# jack_driver_1.net
KiCad netlist of a schematic drawn in Altium Designer
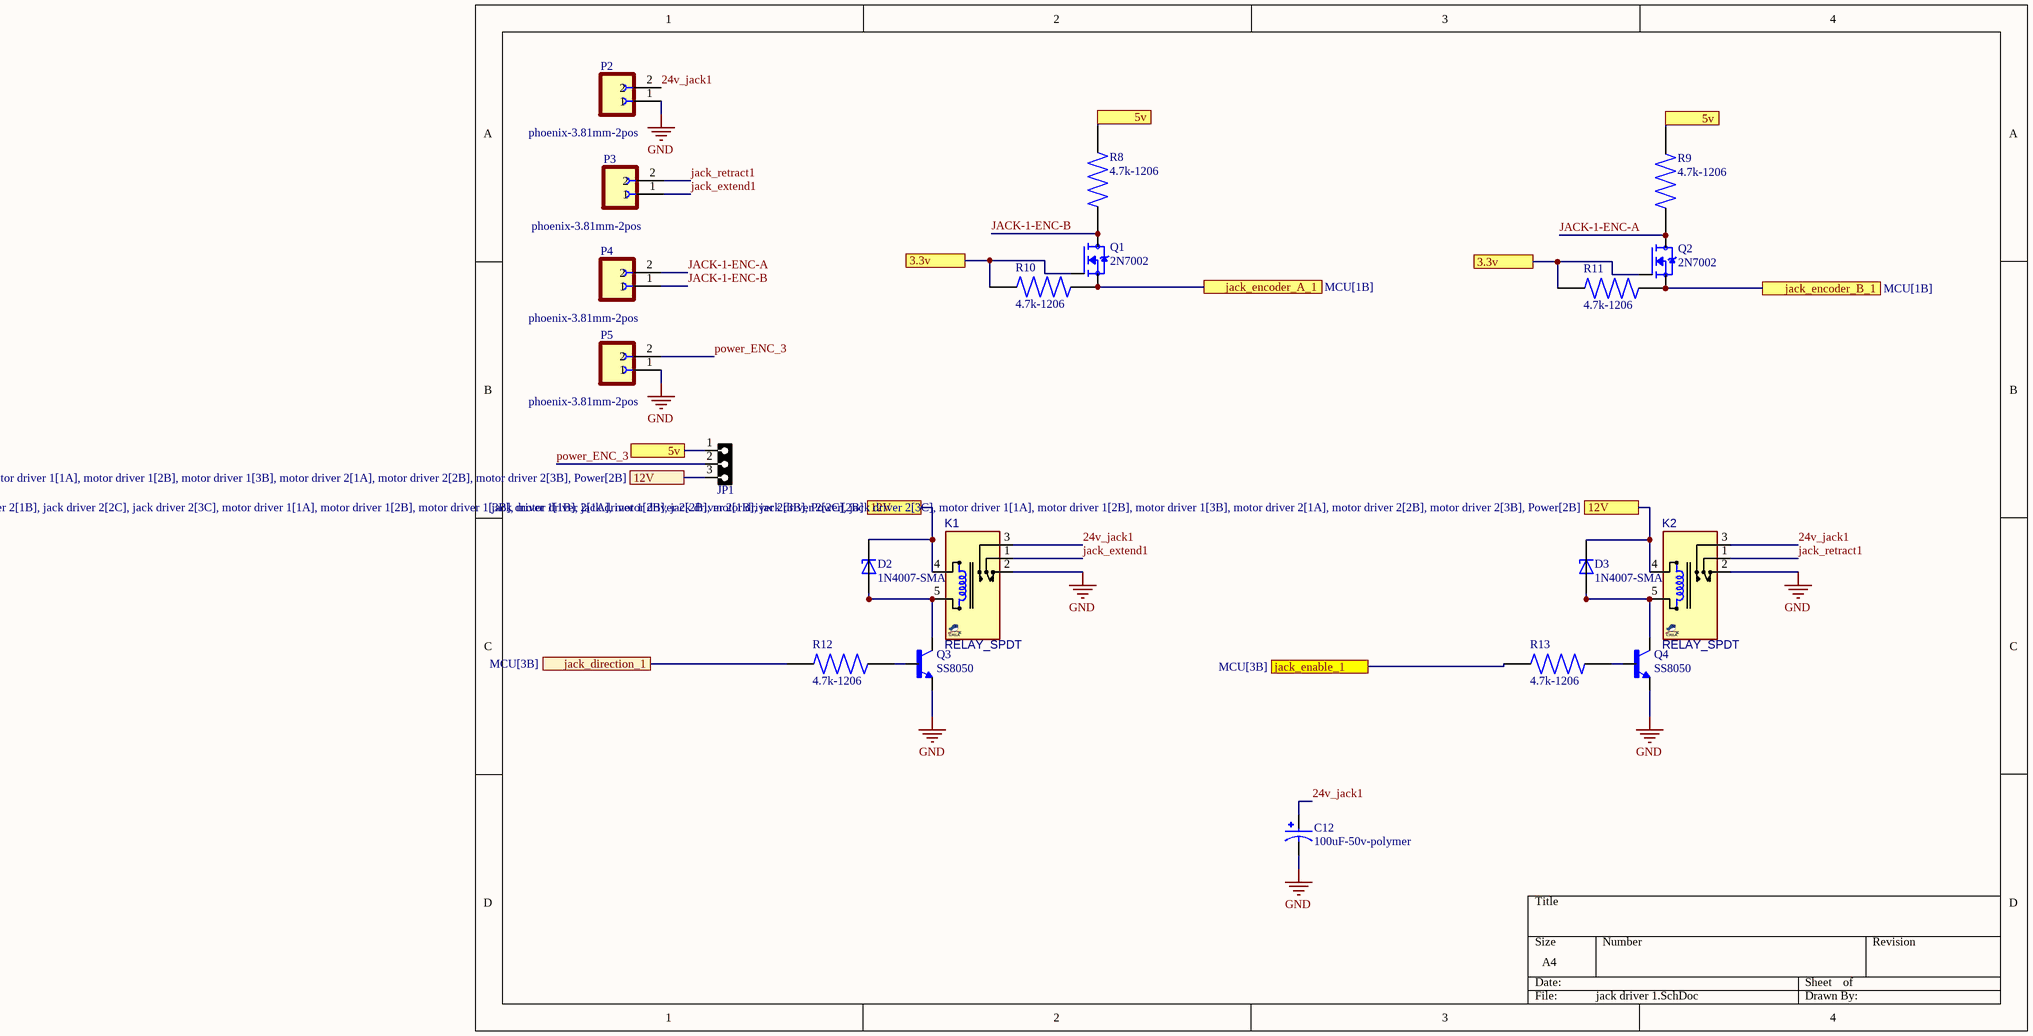
[diagram p0: jack driver 1.SchDoc]

(export (version "E")
  (design (tool "Eeschema 10.0.6"))
  (components
    (comp (ref "C12")
      (value "100uF-50v-polymer")
      (footprint "CAP_EEEFN1H101L")
      (description "CAP ALUM 100UF 20% 50V SMD")
      (fields (field (name "MF") "Panasonic") (field (name "MP") "EEEFN1H101L"))
      (libsource (lib "100uF_50v") (part "EEEFN1H101L"))
    )
    (comp (ref "D2")
      (value "1N4007-SMA")
      (footprint "DIOM4325X250N")
      (description "400W, 30.4V, 5%, Unidirectional, TVS")
      (fields (field (name "MF") "Taiwan Semiconductor") (field (name "MP") "SMAJ26A"))
      (libsource (lib "diode-sma") (part "SMAJ26A"))
    )
    (comp (ref "D3")
      (value "1N4007-SMA")
      (footprint "DIOM4325X250N")
      (description "400W, 30.4V, 5%, Unidirectional, TVS")
      (fields (field (name "MF") "Taiwan Semiconductor") (field (name "MP") "SMAJ26A"))
      (libsource (lib "diode-sma") (part "SMAJ26A"))
    )
    (comp (ref "JP1")
      (value "HDRF3")
      (footprint "HDRLP_F_1X3")
      (description "CONN, HEADER, Male, pitch: 2.54mm, 3POS")
      (libsource (lib "conn_2.54mm_lp") (part "HDRLP_F_1X3"))
    )
    (comp (ref "K1")
      (value "RELAY_SPDT")
      (footprint "REL_SPDT_5_1512")
      (description "Relay, SPDT, 5P, 15.4X12.1mm, 16V/30A")
      (fields (field (name "MANF") "OMRON") (field (name "MANF_P#") "G8QN-1C4 DC12"))
      (libsource (lib "relay") (part "RELAY_SPDT_5_1512_G8QN"))
    )
    (comp (ref "K2")
      (value "RELAY_SPDT")
      (footprint "REL_SPDT_5_1512")
      (description "Relay, SPDT, 5P, 15.4X12.1mm, 16V/30A")
      (fields (field (name "MANF") "OMRON") (field (name "MANF_P#") "G8QN-1C4 DC12"))
      (libsource (lib "relay") (part "RELAY_SPDT_5_1512_G8QN"))
    )
    (comp (ref "P2")
      (value "phoenix-3.81mm-2pos")
      (footprint "PHOENIX_1803578")
      (description "2 Position Terminal Block Plug, Female Sockets 0.150 (3.81mm) 180Â° Free Hanging (In-Line)")
      (fields (field (name "MF") "Phoenix Contact") (field (name "MP") "1803578"))
      (libsource (lib "terminal-phoenix-3.81mm-2pos") (part "1803578"))
    )
    (comp (ref "P3")
      (value "phoenix-3.81mm-2pos")
      (footprint "PHOENIX_1803578")
      (description "2 Position Terminal Block Plug, Female Sockets 0.150 (3.81mm) 180Â° Free Hanging (In-Line)")
      (fields (field (name "MF") "Phoenix Contact") (field (name "MP") "1803578"))
      (libsource (lib "terminal-phoenix-3.81mm-2pos") (part "1803578"))
    )
    (comp (ref "P4")
      (value "phoenix-3.81mm-2pos")
      (footprint "PHOENIX_1803578")
      (description "2 Position Terminal Block Plug, Female Sockets 0.150 (3.81mm) 180Â° Free Hanging (In-Line)")
      (fields (field (name "MF") "Phoenix Contact") (field (name "MP") "1803578"))
      (libsource (lib "terminal-phoenix-3.81mm-2pos") (part "1803578"))
    )
    (comp (ref "P5")
      (value "phoenix-3.81mm-2pos")
      (footprint "PHOENIX_1803578")
      (description "2 Position Terminal Block Plug, Female Sockets 0.150 (3.81mm) 180Â° Free Hanging (In-Line)")
      (fields (field (name "MF") "Phoenix Contact") (field (name "MP") "1803578"))
      (libsource (lib "terminal-phoenix-3.81mm-2pos") (part "1803578"))
    )
    (comp (ref "Q1")
      (value "2N7002")
      (footprint "SOT95P240X111-3N")
      (description "N-Channel 60V 280mA (Ta) 350mW (Ta) Surface Mount SOT-23-3 (TO-236)")
      (fields (field (name "MF") "{'manufacturer': u'onsemi'}"))
      (libsource (lib "2N7002-SOT23") (part "2N7002"))
    )
    (comp (ref "Q2")
      (value "2N7002")
      (footprint "SOT95P240X111-3N")
      (description "N-Channel 60V 280mA (Ta) 350mW (Ta) Surface Mount SOT-23-3 (TO-236)")
      (fields (field (name "MF") "{'manufacturer': u'onsemi'}"))
      (libsource (lib "2N7002-SOT23") (part "2N7002"))
    )
    (comp (ref "Q3")
      (value "SS8050")
      (footprint "TRANS_SS8050-G")
      (description "Bipolar (BJT) Transistor NPN 25 V 1.5 A 100MHz 300 mW Surface Mount SOT-23-3")
      (fields (field (name "DIGI-KEY_PART_NUMBER") "641-1790-2-ND") (field (name "MP") "SS8050G"))
      (libsource (lib "SS8050-G") (part "SS8050-G"))
    )
    (comp (ref "Q4")
      (value "SS8050")
      (footprint "TRANS_SS8050-G")
      (description "Bipolar (BJT) Transistor NPN 25 V 1.5 A 100MHz 300 mW Surface Mount SOT-23-3")
      (fields (field (name "DIGI-KEY_PART_NUMBER") "641-1790-2-ND") (field (name "MP") "SS8050G"))
      (libsource (lib "SS8050-G") (part "SS8050-G"))
    )
    (comp (ref "R8")
      (value "4.7k-1206")
      (footprint "RESC3015X65N")
      (description "Res Thin Film 1206 10K Ohm 0.1% 1/8W Â±25ppm/Â°C Molded SMD SMD Paper T/R")
      (fields (field (name "MF") "TE Connectivity") (field (name "MP") "CPF1206B10KE1"))
      (libsource (lib "resistor-1206") (part "CPF1206B10KE1"))
    )
    (comp (ref "R9")
      (value "4.7k-1206")
      (footprint "RESC3015X65N")
      (description "Res Thin Film 1206 10K Ohm 0.1% 1/8W Â±25ppm/Â°C Molded SMD SMD Paper T/R")
      (fields (field (name "MF") "TE Connectivity") (field (name "MP") "CPF1206B10KE1"))
      (libsource (lib "resistor-1206") (part "CPF1206B10KE1"))
    )
    (comp (ref "R10")
      (value "4.7k-1206")
      (footprint "RESC3015X65N")
      (description "Res Thin Film 1206 10K Ohm 0.1% 1/8W Â±25ppm/Â°C Molded SMD SMD Paper T/R")
      (fields (field (name "MF") "TE Connectivity") (field (name "MP") "CPF1206B10KE1"))
      (libsource (lib "resistor-1206") (part "CPF1206B10KE1"))
    )
    (comp (ref "R11")
      (value "4.7k-1206")
      (footprint "RESC3015X65N")
      (description "Res Thin Film 1206 10K Ohm 0.1% 1/8W Â±25ppm/Â°C Molded SMD SMD Paper T/R")
      (fields (field (name "MF") "TE Connectivity") (field (name "MP") "CPF1206B10KE1"))
      (libsource (lib "resistor-1206") (part "CPF1206B10KE1"))
    )
    (comp (ref "R12")
      (value "4.7k-1206")
      (footprint "RESC3015X65N")
      (description "Res Thin Film 1206 10K Ohm 0.1% 1/8W Â±25ppm/Â°C Molded SMD SMD Paper T/R")
      (fields (field (name "MF") "TE Connectivity") (field (name "MP") "CPF1206B10KE1"))
      (libsource (lib "resistor-1206") (part "CPF1206B10KE1"))
    )
    (comp (ref "R13")
      (value "4.7k-1206")
      (footprint "RESC3015X65N")
      (description "Res Thin Film 1206 10K Ohm 0.1% 1/8W Â±25ppm/Â°C Molded SMD SMD Paper T/R")
      (fields (field (name "MF") "TE Connectivity") (field (name "MP") "CPF1206B10KE1"))
      (libsource (lib "resistor-1206") (part "CPF1206B10KE1"))
    )
  )
  (nets
    (net (code "1") (name "/3.3v") (class "Default")
      (node (ref "Q1") (pin "1") (pinfunction "G_1") (pintype "passive"))
      (node (ref "Q2") (pin "1") (pinfunction "G_1") (pintype "passive"))
      (node (ref "R10") (pin "2") (pinfunction "2_2") (pintype "passive"))
      (node (ref "R11") (pin "2") (pinfunction "2_2") (pintype "passive"))
    )
    (net (code "2") (name "/5v") (class "Default")
      (node (ref "JP1") (pin "1") (pinfunction "1_1") (pintype "passive"))
      (node (ref "R8") (pin "2") (pinfunction "2_2") (pintype "passive"))
      (node (ref "R9") (pin "2") (pinfunction "2_2") (pintype "passive"))
    )
    (net (code "3") (name "/12V") (class "Default")
      (node (ref "D2") (pin "C") (pinfunction "C_C") (pintype "passive"))
      (node (ref "D3") (pin "C") (pinfunction "C_C") (pintype "passive"))
      (node (ref "JP1") (pin "3") (pinfunction "3_3") (pintype "passive"))
      (node (ref "K1") (pin "4") (pinfunction "T1_4") (pintype "passive"))
      (node (ref "K2") (pin "4") (pinfunction "T1_4") (pintype "passive"))
    )
    (net (code "4") (name "/24v_jack1") (class "Default")
      (node (ref "C12") (pin "1") (pinfunction "1_1") (pintype "passive"))
      (node (ref "K1") (pin "3") (pinfunction "NO_3") (pintype "passive"))
      (node (ref "K2") (pin "3") (pinfunction "NO_3") (pintype "passive"))
      (node (ref "P2") (pin "2") (pinfunction "2_2") (pintype "passive"))
    )
    (net (code "5") (name "/JACK-1-ENC-A") (class "Default")
      (node (ref "P4") (pin "2") (pinfunction "2_2") (pintype "passive"))
      (node (ref "Q2") (pin "3") (pinfunction "D_3") (pintype "passive"))
      (node (ref "R9") (pin "1") (pinfunction "1_1") (pintype "passive"))
    )
    (net (code "6") (name "/JACK-1-ENC-B") (class "Default")
      (node (ref "P4") (pin "1") (pinfunction "1_1") (pintype "passive"))
      (node (ref "Q1") (pin "3") (pinfunction "D_3") (pintype "passive"))
      (node (ref "R8") (pin "1") (pinfunction "1_1") (pintype "passive"))
    )
    (net (code "7") (name "/jack_direction_1") (class "Default")
      (node (ref "R12") (pin "2") (pinfunction "2_2") (pintype "passive"))
    )
    (net (code "8") (name "/jack_enable_1") (class "Default")
      (node (ref "R13") (pin "2") (pinfunction "2_2") (pintype "passive"))
    )
    (net (code "9") (name "/jack_encoder_A_1") (class "Default")
      (node (ref "Q1") (pin "2") (pinfunction "S_2") (pintype "passive"))
      (node (ref "R10") (pin "1") (pinfunction "1_1") (pintype "passive"))
    )
    (net (code "10") (name "/jack_encoder_B_1") (class "Default")
      (node (ref "Q2") (pin "2") (pinfunction "S_2") (pintype "passive"))
      (node (ref "R11") (pin "1") (pinfunction "1_1") (pintype "passive"))
    )
    (net (code "11") (name "/jack_extend1") (class "Default")
      (node (ref "K1") (pin "1") (pinfunction "COM_1") (pintype "passive"))
      (node (ref "P3") (pin "1") (pinfunction "1_1") (pintype "passive"))
    )
    (net (code "12") (name "/jack_retract1") (class "Default")
      (node (ref "K2") (pin "1") (pinfunction "COM_1") (pintype "passive"))
      (node (ref "P3") (pin "2") (pinfunction "2_2") (pintype "passive"))
    )
    (net (code "13") (name "/power_ENC_3") (class "Default")
      (node (ref "JP1") (pin "2") (pinfunction "2_2") (pintype "passive"))
      (node (ref "P5") (pin "2") (pinfunction "2_2") (pintype "passive"))
    )
    (net (code "14") (name "GND") (class "Default")
      (node (ref "C12") (pin "2") (pinfunction "2_2") (pintype "passive"))
      (node (ref "K1") (pin "2") (pinfunction "NC_2") (pintype "passive"))
      (node (ref "K2") (pin "2") (pinfunction "NC_2") (pintype "passive"))
      (node (ref "P2") (pin "1") (pinfunction "1_1") (pintype "passive"))
      (node (ref "P5") (pin "1") (pinfunction "1_1") (pintype "passive"))
      (node (ref "Q3") (pin "2") (pinfunction "E_2") (pintype "passive"))
      (node (ref "Q4") (pin "2") (pinfunction "E_2") (pintype "passive"))
    )
    (net (code "15") (name "Net-(K1-T2)") (class "Default")
      (node (ref "D2") (pin "A") (pinfunction "A_A") (pintype "passive"))
      (node (ref "K1") (pin "5") (pinfunction "T2_5") (pintype "passive"))
      (node (ref "Q3") (pin "3") (pinfunction "C_3") (pintype "passive"))
    )
    (net (code "16") (name "Net-(K2-T2)") (class "Default")
      (node (ref "D3") (pin "A") (pinfunction "A_A") (pintype "passive"))
      (node (ref "K2") (pin "5") (pinfunction "T2_5") (pintype "passive"))
      (node (ref "Q4") (pin "3") (pinfunction "C_3") (pintype "passive"))
    )
    (net (code "17") (name "Net-(Q3-B)") (class "Default")
      (node (ref "Q3") (pin "1") (pinfunction "B_1") (pintype "passive"))
      (node (ref "R12") (pin "1") (pinfunction "1_1") (pintype "passive"))
    )
    (net (code "18") (name "Net-(Q4-B)") (class "Default")
      (node (ref "Q4") (pin "1") (pinfunction "B_1") (pintype "passive"))
      (node (ref "R13") (pin "1") (pinfunction "1_1") (pintype "passive"))
    )
  )
)
